# DSO_Counters.net
KiCad netlist of a schematic drawn in Altium Designer
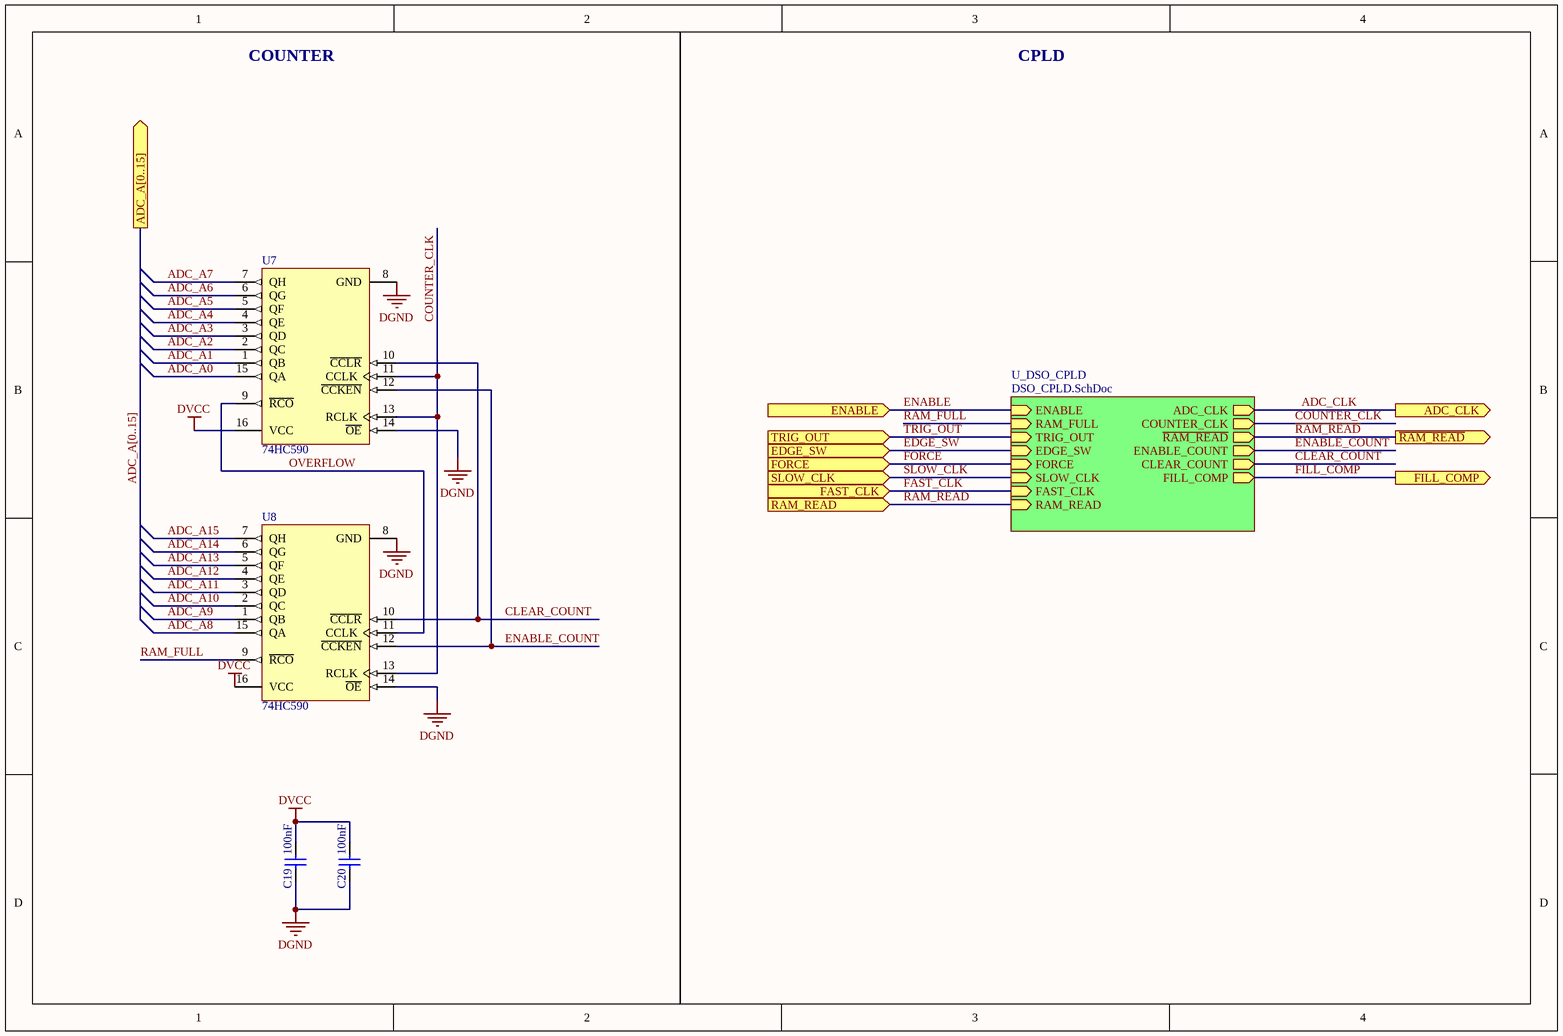
[diagram p0: DSO_Counters.SchDoc]

(export (version "E")
  (design (tool "Eeschema 10.0.6"))
  (components
    (comp (ref "C19")
      (value "100nF")
      (footprint "0805C")
      (description "Capacitor")
      (fields (field (name "REVIEWED BY") "RM - 2018/08/05"))
      (libsource (lib "DSO") (part "C"))
    )
    (comp (ref "C20")
      (value "100nF")
      (footprint "0805C")
      (description "Capacitor")
      (fields (field (name "REVIEWED BY") "RM - 2018/08/05"))
      (libsource (lib "DSO") (part "C"))
    )
    (comp (ref "U7")
      (value "74HC590")
      (footprint "SOIC-16")
      (description "8-Bit Binary Counter Register")
      (fields (field (name "REVIEWED BY") "RM - 2018/08/05"))
      (libsource (lib "DSO") (part "74HC590"))
    )
    (comp (ref "U8")
      (value "74HC590")
      (footprint "SOIC-16")
      (description "8-Bit Binary Counter Register")
      (fields (field (name "REVIEWED BY") "RM - 2018/08/05"))
      (libsource (lib "DSO") (part "74HC590"))
    )
  )
  (nets
    (net (code "1") (name "/ADC_A0") (class "Default")
      (node (ref "U7") (pin "15") (pinfunction "QA_15") (pintype "output"))
    )
    (net (code "2") (name "/ADC_A1") (class "Default")
      (node (ref "U7") (pin "1") (pinfunction "QB_1") (pintype "output"))
    )
    (net (code "3") (name "/ADC_A2") (class "Default")
      (node (ref "U7") (pin "2") (pinfunction "QC_2") (pintype "output"))
    )
    (net (code "4") (name "/ADC_A3") (class "Default")
      (node (ref "U7") (pin "3") (pinfunction "QD_3") (pintype "output"))
    )
    (net (code "5") (name "/ADC_A4") (class "Default")
      (node (ref "U7") (pin "4") (pinfunction "QE_4") (pintype "output"))
    )
    (net (code "6") (name "/ADC_A5") (class "Default")
      (node (ref "U7") (pin "5") (pinfunction "QF_5") (pintype "output"))
    )
    (net (code "7") (name "/ADC_A6") (class "Default")
      (node (ref "U7") (pin "6") (pinfunction "QG_6") (pintype "output"))
    )
    (net (code "8") (name "/ADC_A7") (class "Default")
      (node (ref "U7") (pin "7") (pinfunction "QH_7") (pintype "output"))
    )
    (net (code "9") (name "/ADC_A8") (class "Default")
      (node (ref "U8") (pin "15") (pinfunction "QA_15") (pintype "output"))
    )
    (net (code "10") (name "/ADC_A9") (class "Default")
      (node (ref "U8") (pin "1") (pinfunction "QB_1") (pintype "output"))
    )
    (net (code "11") (name "/ADC_A10") (class "Default")
      (node (ref "U8") (pin "2") (pinfunction "QC_2") (pintype "output"))
    )
    (net (code "12") (name "/ADC_A11") (class "Default")
      (node (ref "U8") (pin "3") (pinfunction "QD_3") (pintype "output"))
    )
    (net (code "13") (name "/ADC_A12") (class "Default")
      (node (ref "U8") (pin "4") (pinfunction "QE_4") (pintype "output"))
    )
    (net (code "14") (name "/ADC_A13") (class "Default")
      (node (ref "U8") (pin "5") (pinfunction "QF_5") (pintype "output"))
    )
    (net (code "15") (name "/ADC_A14") (class "Default")
      (node (ref "U8") (pin "6") (pinfunction "QG_6") (pintype "output"))
    )
    (net (code "16") (name "/ADC_A15") (class "Default")
      (node (ref "U8") (pin "7") (pinfunction "QH_7") (pintype "output"))
    )
    (net (code "19") (name "/CLEAR_COUNT") (class "Default")
      (node (ref "U7") (pin "10") (pinfunction "~{CCLR}_10") (pintype "input"))
      (node (ref "U8") (pin "10") (pinfunction "~{CCLR}_10") (pintype "input"))
    )
    (net (code "20") (name "/COUNTER_CLK") (class "Default")
      (node (ref "U7") (pin "11") (pinfunction "CCLK_11") (pintype "input"))
      (node (ref "U7") (pin "13") (pinfunction "RCLK_13") (pintype "input"))
      (node (ref "U8") (pin "13") (pinfunction "RCLK_13") (pintype "input"))
    )
    (net (code "23") (name "/ENABLE_COUNT") (class "Default")
      (node (ref "U7") (pin "12") (pinfunction "~{CCKEN}_12") (pintype "input"))
      (node (ref "U8") (pin "12") (pinfunction "~{CCKEN}_12") (pintype "input"))
    )
    (net (code "27") (name "/OVERFLOW") (class "Default")
      (node (ref "U7") (pin "9") (pinfunction "~{RCO}_9") (pintype "output"))
      (node (ref "U8") (pin "11") (pinfunction "CCLK_11") (pintype "input"))
    )
    (net (code "28") (name "/RAM_FULL") (class "Default")
      (node (ref "U8") (pin "9") (pinfunction "~{RCO}_9") (pintype "output"))
    )
    (net (code "33") (name "DGND") (class "Default")
      (node (ref "C19") (pin "2") (pinfunction "2_2") (pintype "passive"))
      (node (ref "C20") (pin "2") (pinfunction "2_2") (pintype "passive"))
      (node (ref "U7") (pin "14") (pinfunction "~{OE}_14") (pintype "input"))
      (node (ref "U7") (pin "8") (pinfunction "GND_8") (pintype "power_in"))
      (node (ref "U8") (pin "14") (pinfunction "~{OE}_14") (pintype "input"))
      (node (ref "U8") (pin "8") (pinfunction "GND_8") (pintype "power_in"))
    )
    (net (code "34") (name "DVCC") (class "Default")
      (node (ref "C19") (pin "1") (pinfunction "1_1") (pintype "passive"))
      (node (ref "C20") (pin "1") (pinfunction "1_1") (pintype "passive"))
      (node (ref "U7") (pin "16") (pinfunction "VCC_16") (pintype "power_in"))
      (node (ref "U8") (pin "16") (pinfunction "VCC_16") (pintype "power_in"))
    )
  )
)
